# input_output.net
KiCad netlist of a schematic drawn in Altium Designer
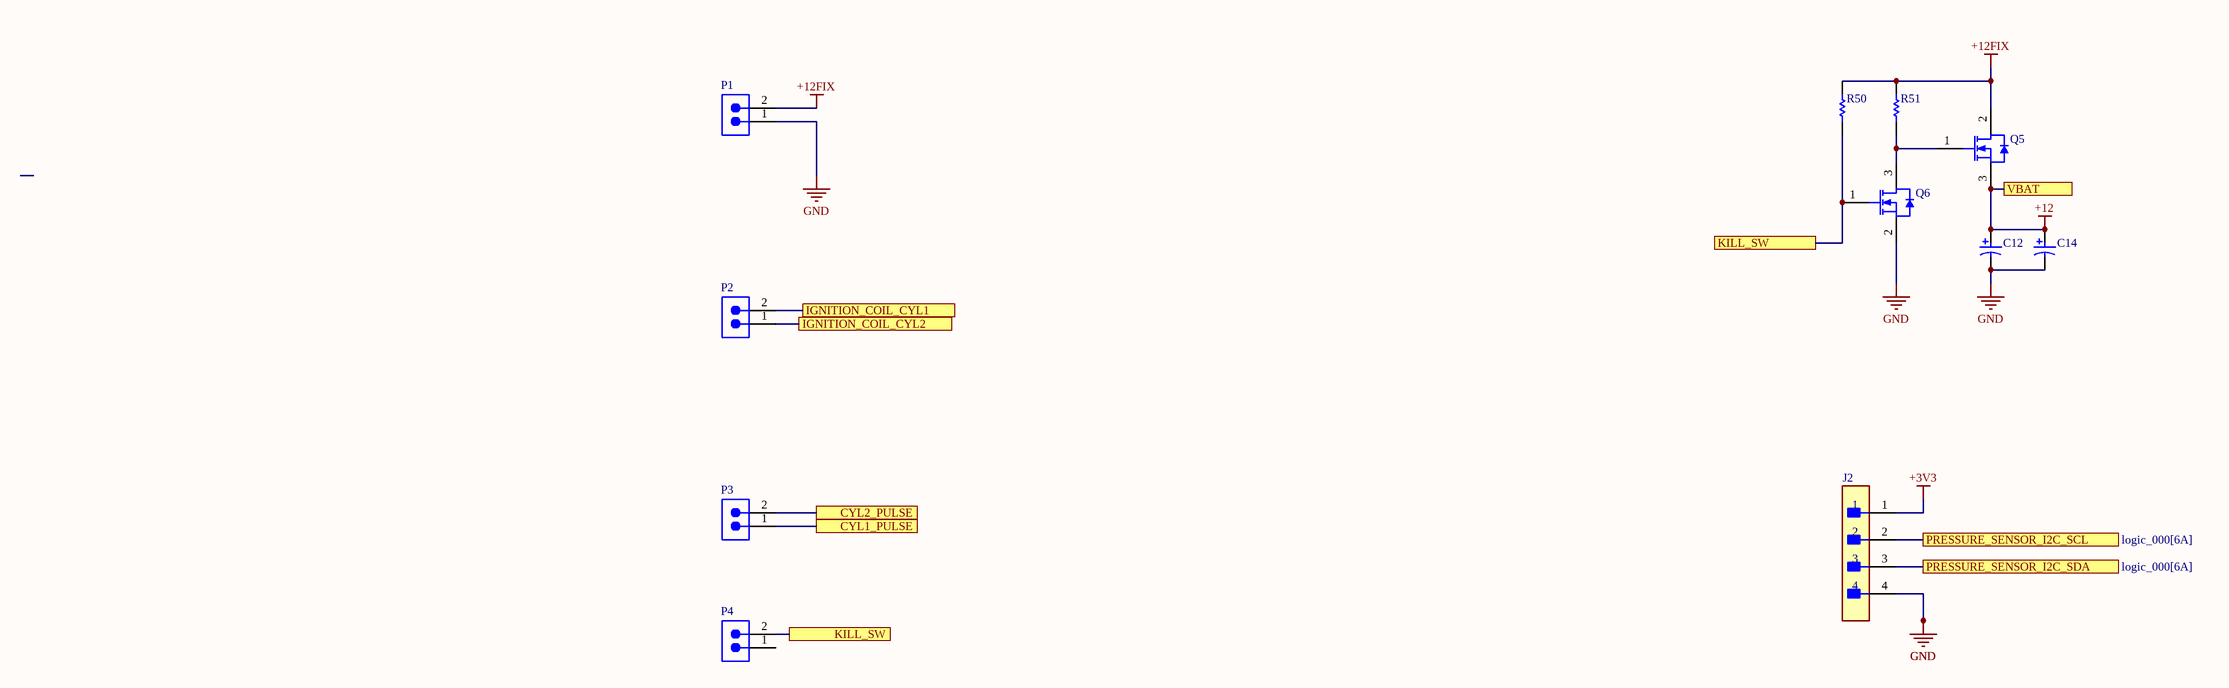
[diagram p0: input_output.SchDoc]

(export (version "E")
  (design (tool "Eeschema 10.0.6"))
  (components
    (comp (ref "C12")
      (value "UUD1A102MNL1GS")
      (footprint "NIC-CAPA2-10X10_V")
      (fields (field (name "MANUFACTURER") "Nichicon"))
      (libsource (lib "Altium Content Vault") (part "NIC-CAP-P-2"))
    )
    (comp (ref "C14")
      (value "UUD1A102MNL1GS")
      (footprint "NIC-CAPA2-10X10_V")
      (fields (field (name "MANUFACTURER") "Nichicon"))
      (libsource (lib "Altium Content Vault") (part "NIC-CAP-P-2"))
    )
    (comp (ref "J2")
      (value "53047-0410")
      (footprint "FP-53047-0410-MFG")
      (description "CONN HEADER VERT 4POS 1.25MM")
      (fields (field (name "VOLTAGE") "125V"))
      (libsource (lib "Altium Content Vault") (part "299a8cea1bdcbc3624fe62c390fa72c"))
    )
    (comp (ref "P1")
      (value "691701510002B")
      (footprint "691701510002B")
      (libsource (lib "Altium Content Vault") (part "TBL - 1R - 02P - Male"))
    )
    (comp (ref "P2")
      (value "691701510002B")
      (footprint "691701510002B")
      (libsource (lib "Altium Content Vault") (part "TBL - 1R - 02P - Male"))
    )
    (comp (ref "P3")
      (value "691701510002B")
      (footprint "691701510002B")
      (libsource (lib "Altium Content Vault") (part "TBL - 1R - 02P - Male"))
    )
    (comp (ref "P4")
      (value "691701510002B")
      (footprint "691701510002B")
      (libsource (lib "Altium Content Vault") (part "TBL - 1R - 02P - Male"))
    )
    (comp (ref "Q5")
      (value "IPD600N25N3")
      (footprint "INF-PG-TO252-3-11_A_L")
      (fields (field (name "PARTNUMBER") "IPD035N06L3 G") (field (name "MANUFACTURER") "Infineon"))
      (libsource (lib "Altium Content Vault") (part "INF-NEMOS-GDS-3"))
    )
    (comp (ref "Q6")
      (value "PMV56XN,215")
      (footprint "NXP-SOT23_L")
      (description "N-Channel uTrenchMOS(TM) Extremely Low Level FET, 20 V, 3.76 A, 3-Pin SOT23, Tape and Reel")
      (fields (field (name "MANUFACTURER") "NXP Semiconductors"))
      (libsource (lib "Altium Content Vault") (part "NXP-NMOS-GSD-3_B"))
    )
    (comp (ref "R50")
      (value "RC0603FR-07470KL")
      (footprint "RESC1608X55X25ML10T15")
      (description "Chip Resistor, 470 KOhm, +/- 1%, 0.1 W, -55 to 155 degC, 0603 (1608 Metric), RoHS, Tape and Reel")
      (libsource (lib "Altium Content Vault") (part "RES-2"))
    )
    (comp (ref "R51")
      (value "RC0603FR-07470KL")
      (footprint "RESC1608X55X25ML10T15")
      (description "Chip Resistor, 470 KOhm, +/- 1%, 0.1 W, -55 to 155 degC, 0603 (1608 Metric), RoHS, Tape and Reel")
      (libsource (lib "Altium Content Vault") (part "RES-2"))
    )
  )
  (nets
    (net (code "1") (name "+3V3") (class "Default")
      (node (ref "J2") (pin "1") (pinfunction "1_1") (pintype "passive"))
    )
    (net (code "2") (name "+12") (class "Default")
      (node (ref "C12") (pin "1") (pinfunction "1_1") (pintype "passive"))
      (node (ref "C14") (pin "1") (pinfunction "1_1") (pintype "passive"))
      (node (ref "Q5") (pin "3") (pinfunction "SOURCE_3") (pintype "passive"))
    )
    (net (code "3") (name "+12FIX") (class "Default")
      (node (ref "P1") (pin "2") (pinfunction "2_2") (pintype "passive"))
      (node (ref "Q5") (pin "2") (pinfunction "DRAIN_2") (pintype "passive"))
      (node (ref "R50") (pin "2") (pinfunction "2_2") (pintype "passive"))
      (node (ref "R51") (pin "2") (pinfunction "2_2") (pintype "passive"))
    )
    (net (code "4") (name "/CYL1_PULSE") (class "Default")
      (node (ref "P3") (pin "1") (pinfunction "1_1") (pintype "passive"))
    )
    (net (code "5") (name "/CYL2_PULSE") (class "Default")
      (node (ref "P3") (pin "2") (pinfunction "2_2") (pintype "passive"))
    )
    (net (code "6") (name "/IGNITION_COIL_CYL1") (class "Default")
      (node (ref "P2") (pin "2") (pinfunction "2_2") (pintype "passive"))
    )
    (net (code "7") (name "/IGNITION_COIL_CYL2") (class "Default")
      (node (ref "P2") (pin "1") (pinfunction "1_1") (pintype "passive"))
    )
    (net (code "8") (name "/KILL_SW") (class "Default")
      (node (ref "P4") (pin "2") (pinfunction "2_2") (pintype "passive"))
      (node (ref "Q6") (pin "1") (pinfunction "G_1") (pintype "passive"))
      (node (ref "R50") (pin "1") (pinfunction "1_1") (pintype "passive"))
    )
    (net (code "9") (name "/PRESSURE_SENSOR_I2C_SCL") (class "Default")
      (node (ref "J2") (pin "2") (pinfunction "2_2") (pintype "passive"))
    )
    (net (code "10") (name "/PRESSURE_SENSOR_I2C_SDA") (class "Default")
      (node (ref "J2") (pin "3") (pinfunction "3_3") (pintype "passive"))
    )
    (net (code "11") (name "GND") (class "Default")
      (node (ref "C12") (pin "2") (pinfunction "2_2") (pintype "passive"))
      (node (ref "C14") (pin "2") (pinfunction "2_2") (pintype "passive"))
      (node (ref "J2") (pin "4") (pinfunction "4_4") (pintype "passive"))
      (node (ref "P1") (pin "1") (pinfunction "1_1") (pintype "passive"))
      (node (ref "Q6") (pin "2") (pinfunction "S_2") (pintype "passive"))
    )
    (net (code "12") (name "Net-(Q5-GATE)") (class "Default")
      (node (ref "Q5") (pin "1") (pinfunction "GATE_1") (pintype "passive"))
      (node (ref "Q6") (pin "3") (pinfunction "D_3") (pintype "passive"))
      (node (ref "R51") (pin "1") (pinfunction "1_1") (pintype "passive"))
    )
    (net (code "13") (name "unconnected-(P4-Pad1)") (class "Default")
      (node (ref "P4") (pin "1") (pinfunction "1_1") (pintype "passive"))
    )
  )
)
